# a52-flashcart.net
KiCad netlist of a schematic drawn in EAGLE
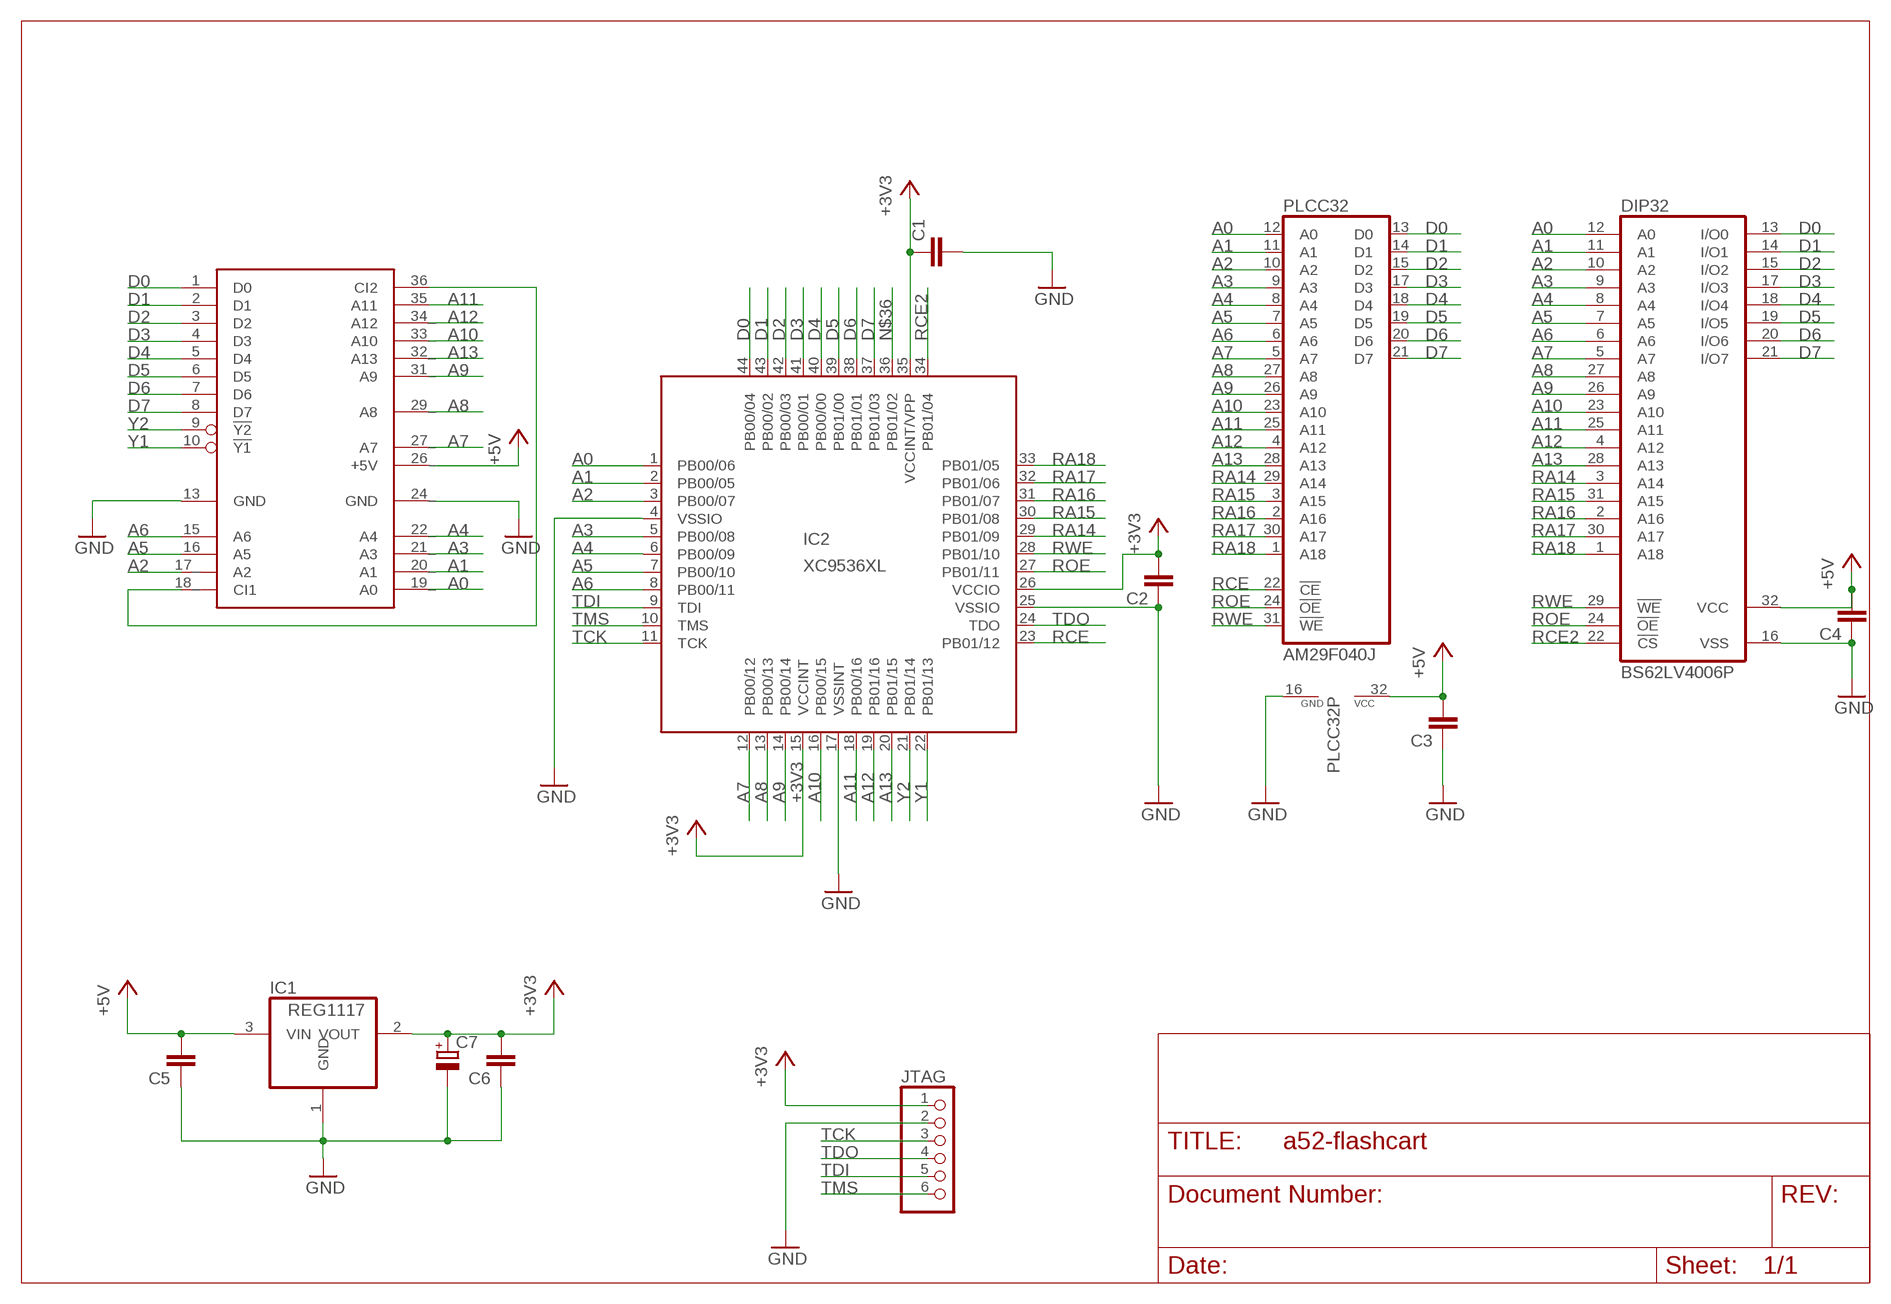
[diagram p0: schematic, sheet 1]

(export (version "E")
  (design (tool "Eeschema 10.0.6"))
  (components
    (comp (ref "C1")
      (value "C-EUC0603")
      (footprint "eagle-import:C0603")
      (libsource (lib "eagle-import") (part "C-EUC0603"))
    )
    (comp (ref "C2")
      (value "C-EUC0603")
      (footprint "eagle-import:C0603")
      (libsource (lib "eagle-import") (part "C-EUC0603"))
    )
    (comp (ref "C3")
      (value "C-EUC0603")
      (footprint "eagle-import:C0603")
      (libsource (lib "eagle-import") (part "C-EUC0603"))
    )
    (comp (ref "C4")
      (value "C-EUC0603")
      (footprint "eagle-import:C0603")
      (libsource (lib "eagle-import") (part "C-EUC0603"))
    )
    (comp (ref "C5")
      (value "C-EUC0603")
      (footprint "eagle-import:C0603")
      (libsource (lib "eagle-import") (part "C-EUC0603"))
    )
    (comp (ref "C6")
      (value "C-EUC0603")
      (footprint "eagle-import:C0603")
      (libsource (lib "eagle-import") (part "C-EUC0603"))
    )
    (comp (ref "C7")
      (value "CPOL-EUE2,5-6E")
      (footprint "eagle-import:E25-6E")
      (libsource (lib "eagle-import") (part "CPOL-EUE2,5-6E"))
    )
    (comp (ref "DIP32")
      (value "BS62LV4006P")
      (footprint "eagle-import:DIL-32")
      (libsource (lib "eagle-import") (part "BS62LV4006P"))
    )
    (comp (ref "IC1")
      (value "REG1117")
      (footprint "eagle-import:SOT223")
      (libsource (lib "eagle-import") (part "REG1117"))
    )
    (comp (ref "IC2")
      (value "XC9536XL")
      (footprint "eagle-import:SQFP-S-10X10-44")
      (fields (field (name "MPN") "XC9536-15VQG44C"))
      (libsource (lib "eagle-import") (part "XC9536_44VQ"))
    )
    (comp (ref "JTAG")
      (value "PINHD-1X6")
      (footprint "eagle-import:1X06")
      (libsource (lib "eagle-import") (part "PINHD-1X6"))
    )
    (comp (ref "PLCC32")
      (value "AM29F040J")
      (footprint "eagle-import:PLCC32R")
      (libsource (lib "eagle-import") (part "AM29F040J"))
    )
    (comp (ref "U$1")
      (value "ATARI-5200")
      (footprint "eagle-import:ATARI-5200")
      (libsource (lib "eagle-import") (part "ATARI-5200"))
    )
  )
  (nets
    (net (code "1") (name "+3V3") (class "Default")
      (node (ref "C1") (pin "1") (pinfunction "1_1") (pintype "passive"))
      (node (ref "C2") (pin "2") (pinfunction "2_2") (pintype "passive"))
      (node (ref "C6") (pin "2") (pinfunction "2_2") (pintype "passive"))
      (node (ref "C7") (pin "+") (pinfunction "+_+") (pintype "passive"))
      (node (ref "IC1") (pin "2") (pinfunction "VOUT_2") (pintype "output"))
      (node (ref "IC2") (pin "15") (pinfunction "VCCINT_15") (pintype "power_in"))
      (node (ref "IC2") (pin "26") (pinfunction "VCCIO_26") (pintype "power_in"))
      (node (ref "IC2") (pin "35") (pinfunction "VCCINT/VPP_35") (pintype "input"))
      (node (ref "JTAG") (pin "1") (pinfunction "1_1") (pintype "passive"))
    )
    (net (code "2") (name "+5V") (class "Default")
      (node (ref "C3") (pin "2") (pinfunction "2_2") (pintype "passive"))
      (node (ref "C4") (pin "2") (pinfunction "2_2") (pintype "passive"))
      (node (ref "C5") (pin "2") (pinfunction "2_2") (pintype "passive"))
      (node (ref "DIP32") (pin "32") (pinfunction "VCC_32") (pintype "power_in"))
      (node (ref "IC1") (pin "3") (pinfunction "VIN_3") (pintype "input"))
      (node (ref "PLCC32") (pin "32") (pinfunction "VCC_32") (pintype "power_in"))
      (node (ref "U$1") (pin "26_") (pinfunction "+5V_26_") (pintype "bidirectional"))
    )
    (net (code "3") (name "/A0") (class "Default")
      (node (ref "DIP32") (pin "12") (pinfunction "A0_12") (pintype "input"))
      (node (ref "IC2") (pin "1") (pinfunction "PB00/06_1") (pintype "bidirectional"))
      (node (ref "PLCC32") (pin "12") (pinfunction "A0_12") (pintype "input"))
      (node (ref "U$1") (pin "19_") (pinfunction "A0_19_") (pintype "bidirectional"))
    )
    (net (code "4") (name "/A1") (class "Default")
      (node (ref "DIP32") (pin "11") (pinfunction "A1_11") (pintype "input"))
      (node (ref "IC2") (pin "2") (pinfunction "PB00/05_2") (pintype "bidirectional"))
      (node (ref "PLCC32") (pin "11") (pinfunction "A1_11") (pintype "input"))
      (node (ref "U$1") (pin "20_") (pinfunction "A1_20_") (pintype "bidirectional"))
    )
    (net (code "5") (name "/A2") (class "Default")
      (node (ref "DIP32") (pin "10") (pinfunction "A2_10") (pintype "input"))
      (node (ref "IC2") (pin "3") (pinfunction "PB00/07_3") (pintype "bidirectional"))
      (node (ref "PLCC32") (pin "10") (pinfunction "A2_10") (pintype "input"))
      (node (ref "U$1") (pin "17_") (pinfunction "A2_17_") (pintype "bidirectional"))
    )
    (net (code "6") (name "/A3") (class "Default")
      (node (ref "DIP32") (pin "9") (pinfunction "A3_9") (pintype "input"))
      (node (ref "IC2") (pin "5") (pinfunction "PB00/08_5") (pintype "bidirectional"))
      (node (ref "PLCC32") (pin "9") (pinfunction "A3_9") (pintype "input"))
      (node (ref "U$1") (pin "21_") (pinfunction "A3_21_") (pintype "bidirectional"))
    )
    (net (code "7") (name "/A4") (class "Default")
      (node (ref "DIP32") (pin "8") (pinfunction "A4_8") (pintype "input"))
      (node (ref "IC2") (pin "6") (pinfunction "PB00/09_6") (pintype "bidirectional"))
      (node (ref "PLCC32") (pin "8") (pinfunction "A4_8") (pintype "input"))
      (node (ref "U$1") (pin "22_") (pinfunction "A4_22_") (pintype "bidirectional"))
    )
    (net (code "8") (name "/A5") (class "Default")
      (node (ref "DIP32") (pin "7") (pinfunction "A5_7") (pintype "input"))
      (node (ref "IC2") (pin "7") (pinfunction "PB00/10_7") (pintype "bidirectional"))
      (node (ref "PLCC32") (pin "7") (pinfunction "A5_7") (pintype "input"))
      (node (ref "U$1") (pin "16") (pinfunction "A5_16") (pintype "bidirectional"))
    )
    (net (code "9") (name "/A6") (class "Default")
      (node (ref "DIP32") (pin "6") (pinfunction "A6_6") (pintype "input"))
      (node (ref "IC2") (pin "8") (pinfunction "PB00/11_8") (pintype "bidirectional"))
      (node (ref "PLCC32") (pin "6") (pinfunction "A6_6") (pintype "input"))
      (node (ref "U$1") (pin "15") (pinfunction "A6_15") (pintype "bidirectional"))
    )
    (net (code "10") (name "/A7") (class "Default")
      (node (ref "DIP32") (pin "5") (pinfunction "A7_5") (pintype "input"))
      (node (ref "IC2") (pin "12") (pinfunction "PB00/12_12") (pintype "bidirectional"))
      (node (ref "PLCC32") (pin "5") (pinfunction "A7_5") (pintype "input"))
      (node (ref "U$1") (pin "27_") (pinfunction "A7_27_") (pintype "bidirectional"))
    )
    (net (code "11") (name "/A8") (class "Default")
      (node (ref "DIP32") (pin "27") (pinfunction "A8_27") (pintype "input"))
      (node (ref "IC2") (pin "13") (pinfunction "PB00/13_13") (pintype "bidirectional"))
      (node (ref "PLCC32") (pin "27") (pinfunction "A8_27") (pintype "input"))
      (node (ref "U$1") (pin "29_") (pinfunction "A8_29_") (pintype "bidirectional"))
    )
    (net (code "12") (name "/A9") (class "Default")
      (node (ref "DIP32") (pin "26") (pinfunction "A9_26") (pintype "input"))
      (node (ref "IC2") (pin "14") (pinfunction "PB00/14_14") (pintype "bidirectional"))
      (node (ref "PLCC32") (pin "26") (pinfunction "A9_26") (pintype "input"))
      (node (ref "U$1") (pin "31_") (pinfunction "A9_31_") (pintype "bidirectional"))
    )
    (net (code "13") (name "/A10") (class "Default")
      (node (ref "DIP32") (pin "23") (pinfunction "A10_23") (pintype "input"))
      (node (ref "IC2") (pin "16") (pinfunction "PB00/15_16") (pintype "bidirectional"))
      (node (ref "PLCC32") (pin "23") (pinfunction "A10_23") (pintype "input"))
      (node (ref "U$1") (pin "33_") (pinfunction "A10_33_") (pintype "bidirectional"))
    )
    (net (code "14") (name "/A11") (class "Default")
      (node (ref "DIP32") (pin "25") (pinfunction "A11_25") (pintype "input"))
      (node (ref "IC2") (pin "18") (pinfunction "PB00/16_18") (pintype "bidirectional"))
      (node (ref "PLCC32") (pin "25") (pinfunction "A11_25") (pintype "input"))
      (node (ref "U$1") (pin "35") (pinfunction "A11_35") (pintype "bidirectional"))
    )
    (net (code "15") (name "/A12") (class "Default")
      (node (ref "DIP32") (pin "4") (pinfunction "A12_4") (pintype "input"))
      (node (ref "IC2") (pin "19") (pinfunction "PB01/16_19") (pintype "bidirectional"))
      (node (ref "PLCC32") (pin "4") (pinfunction "A12_4") (pintype "input"))
      (node (ref "U$1") (pin "34_") (pinfunction "A12_34_") (pintype "bidirectional"))
    )
    (net (code "16") (name "/A13") (class "Default")
      (node (ref "DIP32") (pin "28") (pinfunction "A13_28") (pintype "input"))
      (node (ref "IC2") (pin "20") (pinfunction "PB01/15_20") (pintype "bidirectional"))
      (node (ref "PLCC32") (pin "28") (pinfunction "A13_28") (pintype "input"))
      (node (ref "U$1") (pin "32_") (pinfunction "A13_32_") (pintype "bidirectional"))
    )
    (net (code "17") (name "/D0") (class "Default")
      (node (ref "DIP32") (pin "13") (pinfunction "I/O0_13") (pintype "bidirectional"))
      (node (ref "IC2") (pin "44") (pinfunction "PB00/04_44") (pintype "bidirectional"))
      (node (ref "PLCC32") (pin "13") (pinfunction "D0_13") (pintype "tri_state"))
      (node (ref "U$1") (pin "1") (pinfunction "D0_1") (pintype "bidirectional"))
    )
    (net (code "18") (name "/D1") (class "Default")
      (node (ref "DIP32") (pin "14") (pinfunction "I/O1_14") (pintype "bidirectional"))
      (node (ref "IC2") (pin "43") (pinfunction "PB00/02_43") (pintype "bidirectional"))
      (node (ref "PLCC32") (pin "14") (pinfunction "D1_14") (pintype "tri_state"))
      (node (ref "U$1") (pin "2") (pinfunction "D1_2") (pintype "bidirectional"))
    )
    (net (code "19") (name "/D2") (class "Default")
      (node (ref "DIP32") (pin "15") (pinfunction "I/O2_15") (pintype "bidirectional"))
      (node (ref "IC2") (pin "42") (pinfunction "PB00/03_42") (pintype "bidirectional"))
      (node (ref "PLCC32") (pin "15") (pinfunction "D2_15") (pintype "tri_state"))
      (node (ref "U$1") (pin "3") (pinfunction "D2_3") (pintype "bidirectional"))
    )
    (net (code "20") (name "/D3") (class "Default")
      (node (ref "DIP32") (pin "17") (pinfunction "I/O3_17") (pintype "bidirectional"))
      (node (ref "IC2") (pin "41") (pinfunction "PB00/01_41") (pintype "bidirectional"))
      (node (ref "PLCC32") (pin "17") (pinfunction "D3_17") (pintype "tri_state"))
      (node (ref "U$1") (pin "4") (pinfunction "D3_4") (pintype "bidirectional"))
    )
    (net (code "21") (name "/D4") (class "Default")
      (node (ref "DIP32") (pin "18") (pinfunction "I/O4_18") (pintype "bidirectional"))
      (node (ref "IC2") (pin "40") (pinfunction "PB00/00_40") (pintype "bidirectional"))
      (node (ref "PLCC32") (pin "18") (pinfunction "D4_18") (pintype "tri_state"))
      (node (ref "U$1") (pin "5") (pinfunction "D4_5") (pintype "bidirectional"))
    )
    (net (code "22") (name "/D5") (class "Default")
      (node (ref "DIP32") (pin "19") (pinfunction "I/O5_19") (pintype "bidirectional"))
      (node (ref "IC2") (pin "39") (pinfunction "PB01/00_39") (pintype "bidirectional"))
      (node (ref "PLCC32") (pin "19") (pinfunction "D5_19") (pintype "tri_state"))
      (node (ref "U$1") (pin "6") (pinfunction "D5_6") (pintype "bidirectional"))
    )
    (net (code "23") (name "/D6") (class "Default")
      (node (ref "DIP32") (pin "20") (pinfunction "I/O6_20") (pintype "bidirectional"))
      (node (ref "IC2") (pin "38") (pinfunction "PB01/01_38") (pintype "bidirectional"))
      (node (ref "PLCC32") (pin "20") (pinfunction "D6_20") (pintype "tri_state"))
      (node (ref "U$1") (pin "7") (pinfunction "D6_7") (pintype "bidirectional"))
    )
    (net (code "24") (name "/D7") (class "Default")
      (node (ref "DIP32") (pin "21") (pinfunction "I/O7_21") (pintype "bidirectional"))
      (node (ref "IC2") (pin "37") (pinfunction "PB01/03_37") (pintype "bidirectional"))
      (node (ref "PLCC32") (pin "21") (pinfunction "D7_21") (pintype "tri_state"))
      (node (ref "U$1") (pin "8") (pinfunction "D7_8") (pintype "bidirectional"))
    )
    (net (code "25") (name "/N$36") (class "Default")
      (node (ref "IC2") (pin "36") (pinfunction "PB01/02_36") (pintype "bidirectional"))
    )
    (net (code "26") (name "/RA14") (class "Default")
      (node (ref "DIP32") (pin "3") (pinfunction "A14_3") (pintype "input"))
      (node (ref "IC2") (pin "29") (pinfunction "PB01/09_29") (pintype "bidirectional"))
      (node (ref "PLCC32") (pin "29") (pinfunction "A14_29") (pintype "input"))
    )
    (net (code "27") (name "/RA15") (class "Default")
      (node (ref "DIP32") (pin "31") (pinfunction "A15_31") (pintype "input"))
      (node (ref "IC2") (pin "30") (pinfunction "PB01/08_30") (pintype "bidirectional"))
      (node (ref "PLCC32") (pin "3") (pinfunction "A15_3") (pintype "input"))
    )
    (net (code "28") (name "/RA16") (class "Default")
      (node (ref "DIP32") (pin "2") (pinfunction "A16_2") (pintype "input"))
      (node (ref "IC2") (pin "31") (pinfunction "PB01/07_31") (pintype "bidirectional"))
      (node (ref "PLCC32") (pin "2") (pinfunction "A16_2") (pintype "input"))
    )
    (net (code "29") (name "/RA17") (class "Default")
      (node (ref "DIP32") (pin "30") (pinfunction "A17_30") (pintype "input"))
      (node (ref "IC2") (pin "32") (pinfunction "PB01/06_32") (pintype "bidirectional"))
      (node (ref "PLCC32") (pin "30") (pinfunction "A17_30") (pintype "input"))
    )
    (net (code "30") (name "/RA18") (class "Default")
      (node (ref "DIP32") (pin "1") (pinfunction "A18_1") (pintype "input"))
      (node (ref "IC2") (pin "33") (pinfunction "PB01/05_33") (pintype "bidirectional"))
      (node (ref "PLCC32") (pin "1") (pinfunction "A18_1") (pintype "input"))
    )
    (net (code "31") (name "/RCE") (class "Default")
      (node (ref "IC2") (pin "23") (pinfunction "PB01/12_23") (pintype "bidirectional"))
      (node (ref "PLCC32") (pin "22") (pinfunction "~{CE}_22") (pintype "input"))
    )
    (net (code "32") (name "/RCE2") (class "Default")
      (node (ref "DIP32") (pin "22") (pinfunction "~{CS}_22") (pintype "input"))
      (node (ref "IC2") (pin "34") (pinfunction "PB01/04_34") (pintype "bidirectional"))
    )
    (net (code "33") (name "/ROE") (class "Default")
      (node (ref "DIP32") (pin "24") (pinfunction "~{OE}_24") (pintype "input"))
      (node (ref "IC2") (pin "27") (pinfunction "PB01/11_27") (pintype "bidirectional"))
      (node (ref "PLCC32") (pin "24") (pinfunction "~{OE}_24") (pintype "input"))
    )
    (net (code "34") (name "/RWE") (class "Default")
      (node (ref "DIP32") (pin "29") (pinfunction "~{WE}_29") (pintype "input"))
      (node (ref "IC2") (pin "28") (pinfunction "PB01/10_28") (pintype "bidirectional"))
      (node (ref "PLCC32") (pin "31") (pinfunction "~{WE}_31") (pintype "input"))
    )
    (net (code "35") (name "/TCK") (class "Default")
      (node (ref "IC2") (pin "11") (pinfunction "TCK_11") (pintype "input"))
      (node (ref "JTAG") (pin "3") (pinfunction "3_3") (pintype "passive"))
    )
    (net (code "36") (name "/TDI") (class "Default")
      (node (ref "IC2") (pin "9") (pinfunction "TDI_9") (pintype "input"))
      (node (ref "JTAG") (pin "5") (pinfunction "5_5") (pintype "passive"))
    )
    (net (code "37") (name "/TDO") (class "Default")
      (node (ref "IC2") (pin "24") (pinfunction "TDO_24") (pintype "output"))
      (node (ref "JTAG") (pin "4") (pinfunction "4_4") (pintype "passive"))
    )
    (net (code "38") (name "/TMS") (class "Default")
      (node (ref "IC2") (pin "10") (pinfunction "TMS_10") (pintype "input"))
      (node (ref "JTAG") (pin "6") (pinfunction "6_6") (pintype "passive"))
    )
    (net (code "39") (name "/Y1") (class "Default")
      (node (ref "IC2") (pin "22") (pinfunction "PB01/13_22") (pintype "bidirectional"))
      (node (ref "U$1") (pin "10") (pinfunction "~{Y1}_10") (pintype "bidirectional"))
    )
    (net (code "40") (name "/Y2") (class "Default")
      (node (ref "IC2") (pin "21") (pinfunction "PB01/14_21") (pintype "bidirectional"))
      (node (ref "U$1") (pin "9") (pinfunction "~{Y2}_9") (pintype "bidirectional"))
    )
    (net (code "41") (name "GND") (class "Default")
      (node (ref "C1") (pin "2") (pinfunction "2_2") (pintype "passive"))
      (node (ref "C2") (pin "1") (pinfunction "1_1") (pintype "passive"))
      (node (ref "C3") (pin "1") (pinfunction "1_1") (pintype "passive"))
      (node (ref "C4") (pin "1") (pinfunction "1_1") (pintype "passive"))
      (node (ref "C5") (pin "1") (pinfunction "1_1") (pintype "passive"))
      (node (ref "C6") (pin "1") (pinfunction "1_1") (pintype "passive"))
      (node (ref "C7") (pin "-") (pinfunction "-_-") (pintype "passive"))
      (node (ref "DIP32") (pin "16") (pinfunction "VSS_16") (pintype "power_in"))
      (node (ref "IC1") (pin "1") (pinfunction "GND_1") (pintype "power_in"))
      (node (ref "IC2") (pin "17") (pinfunction "VSSINT_17") (pintype "power_in"))
      (node (ref "IC2") (pin "25") (pinfunction "VSSIO_25") (pintype "power_in"))
      (node (ref "IC2") (pin "4") (pinfunction "VSSIO_4") (pintype "power_in"))
      (node (ref "JTAG") (pin "2") (pinfunction "2_2") (pintype "passive"))
      (node (ref "PLCC32") (pin "16") (pinfunction "GND_16") (pintype "power_in"))
      (node (ref "U$1") (pin "13") (pinfunction "GND_13") (pintype "bidirectional"))
      (node (ref "U$1") (pin "24_") (pinfunction "GND_24_") (pintype "bidirectional"))
    )
    (net (code "42") (name "Net-(U$1-CI1)") (class "Default")
      (node (ref "U$1") (pin "18_") (pinfunction "CI1_18_") (pintype "bidirectional"))
      (node (ref "U$1") (pin "36") (pinfunction "CI2_36") (pintype "bidirectional"))
    )
  )
)
